# Ldo_16V5_15V0.net
KiCad netlist of a schematic drawn in Altium Designer
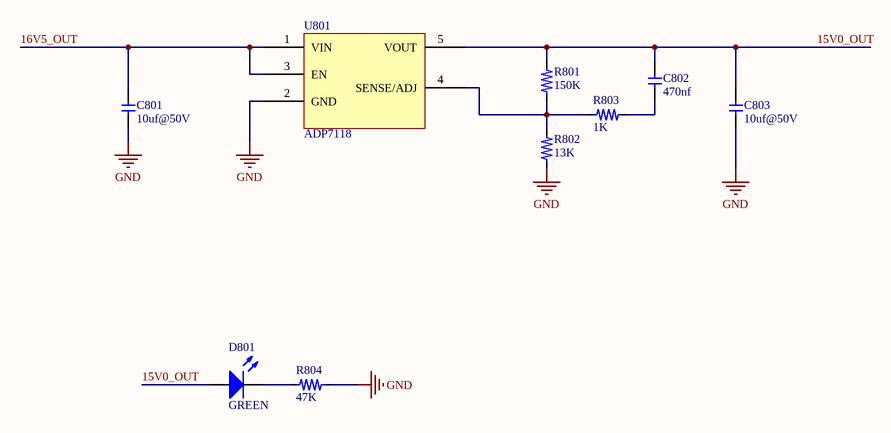
[diagram p0: Ldo.+16V5.+15V0.SchDoc]

(export (version "E")
  (design (tool "Eeschema 10.0.6"))
  (components
    (comp (ref "C801")
      (value "10uf@50V")
      (footprint "C1210")
      (fields (field (name "Comment") "Cap"))
      (libsource (lib "carrot_lib") (part "Cap"))
    )
    (comp (ref "C802")
      (value "470nf")
      (footprint "C0603")
      (fields (field (name "Comment") "Cap"))
      (libsource (lib "carrot_lib") (part "Cap"))
    )
    (comp (ref "C803")
      (value "10uf@50V")
      (footprint "C1210")
      (fields (field (name "Comment") "Cap"))
      (libsource (lib "carrot_lib") (part "Cap"))
    )
    (comp (ref "D801")
      (value "GREEN")
      (footprint "LED0603")
      (fields (field (name "Comment") "LED"))
      (libsource (lib "carrot_lib") (part "LED"))
    )
    (comp (ref "R801")
      (value "150K")
      (footprint "R0603")
      (description "电阻")
      (fields (field (name "Comment") "Res"))
      (libsource (lib "carrot_lib") (part "Res"))
    )
    (comp (ref "R802")
      (value "13K")
      (footprint "R0603")
      (description "电阻")
      (fields (field (name "Comment") "Res"))
      (libsource (lib "carrot_lib") (part "Res"))
    )
    (comp (ref "R803")
      (value "1K")
      (footprint "R0603")
      (description "电阻")
      (fields (field (name "Comment") "Res"))
      (libsource (lib "carrot_lib") (part "Res"))
    )
    (comp (ref "R804")
      (value "47K")
      (footprint "R0603")
      (description "电阻")
      (fields (field (name "Comment") "Res"))
      (libsource (lib "carrot_lib") (part "Res"))
    )
    (comp (ref "U801")
      (value "ADP7118")
      (footprint "ADP7118-TSOT5")
      (description "20 V, 200 mA, Low Noise,CMOS LDO Linear Regulator.")
      (libsource (lib "carrot_lib") (part "ADP7118AUJ"))
    )
  )
  (nets
    (net (code "1") (name "/15V0_OUT") (class "Default")
      (node (ref "C802") (pin "1") (pinfunction "1_1") (pintype "passive"))
      (node (ref "C803") (pin "2") (pinfunction "2_2") (pintype "passive"))
      (node (ref "D801") (pin "1") (pinfunction "A_1") (pintype "passive"))
      (node (ref "R801") (pin "2") (pinfunction "2_2") (pintype "passive"))
      (node (ref "U801") (pin "5") (pinfunction "VOUT_5") (pintype "passive"))
    )
    (net (code "2") (name "/16V5_OUT") (class "Default")
      (node (ref "C801") (pin "2") (pinfunction "2_2") (pintype "passive"))
      (node (ref "U801") (pin "1") (pinfunction "VIN_1") (pintype "passive"))
      (node (ref "U801") (pin "3") (pinfunction "EN_3") (pintype "passive"))
    )
    (net (code "3") (name "GND") (class "Default")
      (node (ref "C801") (pin "1") (pinfunction "1_1") (pintype "passive"))
      (node (ref "C803") (pin "1") (pinfunction "1_1") (pintype "passive"))
      (node (ref "R802") (pin "1") (pinfunction "1_1") (pintype "passive"))
      (node (ref "R804") (pin "1") (pinfunction "1_1") (pintype "passive"))
      (node (ref "U801") (pin "2") (pinfunction "GND_2") (pintype "passive"))
    )
    (net (code "4") (name "Net-(C802-Pad2)") (class "Default")
      (node (ref "C802") (pin "2") (pinfunction "2_2") (pintype "passive"))
      (node (ref "R803") (pin "1") (pinfunction "1_1") (pintype "passive"))
    )
    (net (code "5") (name "Net-(D801-K)") (class "Default")
      (node (ref "D801") (pin "2") (pinfunction "K_2") (pintype "passive"))
      (node (ref "R804") (pin "2") (pinfunction "2_2") (pintype "passive"))
    )
    (net (code "6") (name "Net-(U801-SENSE{slash}ADJ)") (class "Default")
      (node (ref "R801") (pin "1") (pinfunction "1_1") (pintype "passive"))
      (node (ref "R802") (pin "2") (pinfunction "2_2") (pintype "passive"))
      (node (ref "R803") (pin "2") (pinfunction "2_2") (pintype "passive"))
      (node (ref "U801") (pin "4") (pinfunction "SENSE/ADJ_4") (pintype "passive"))
    )
  )
)
